# ZynqPS.net
KiCad netlist of a schematic drawn in Altium Designer
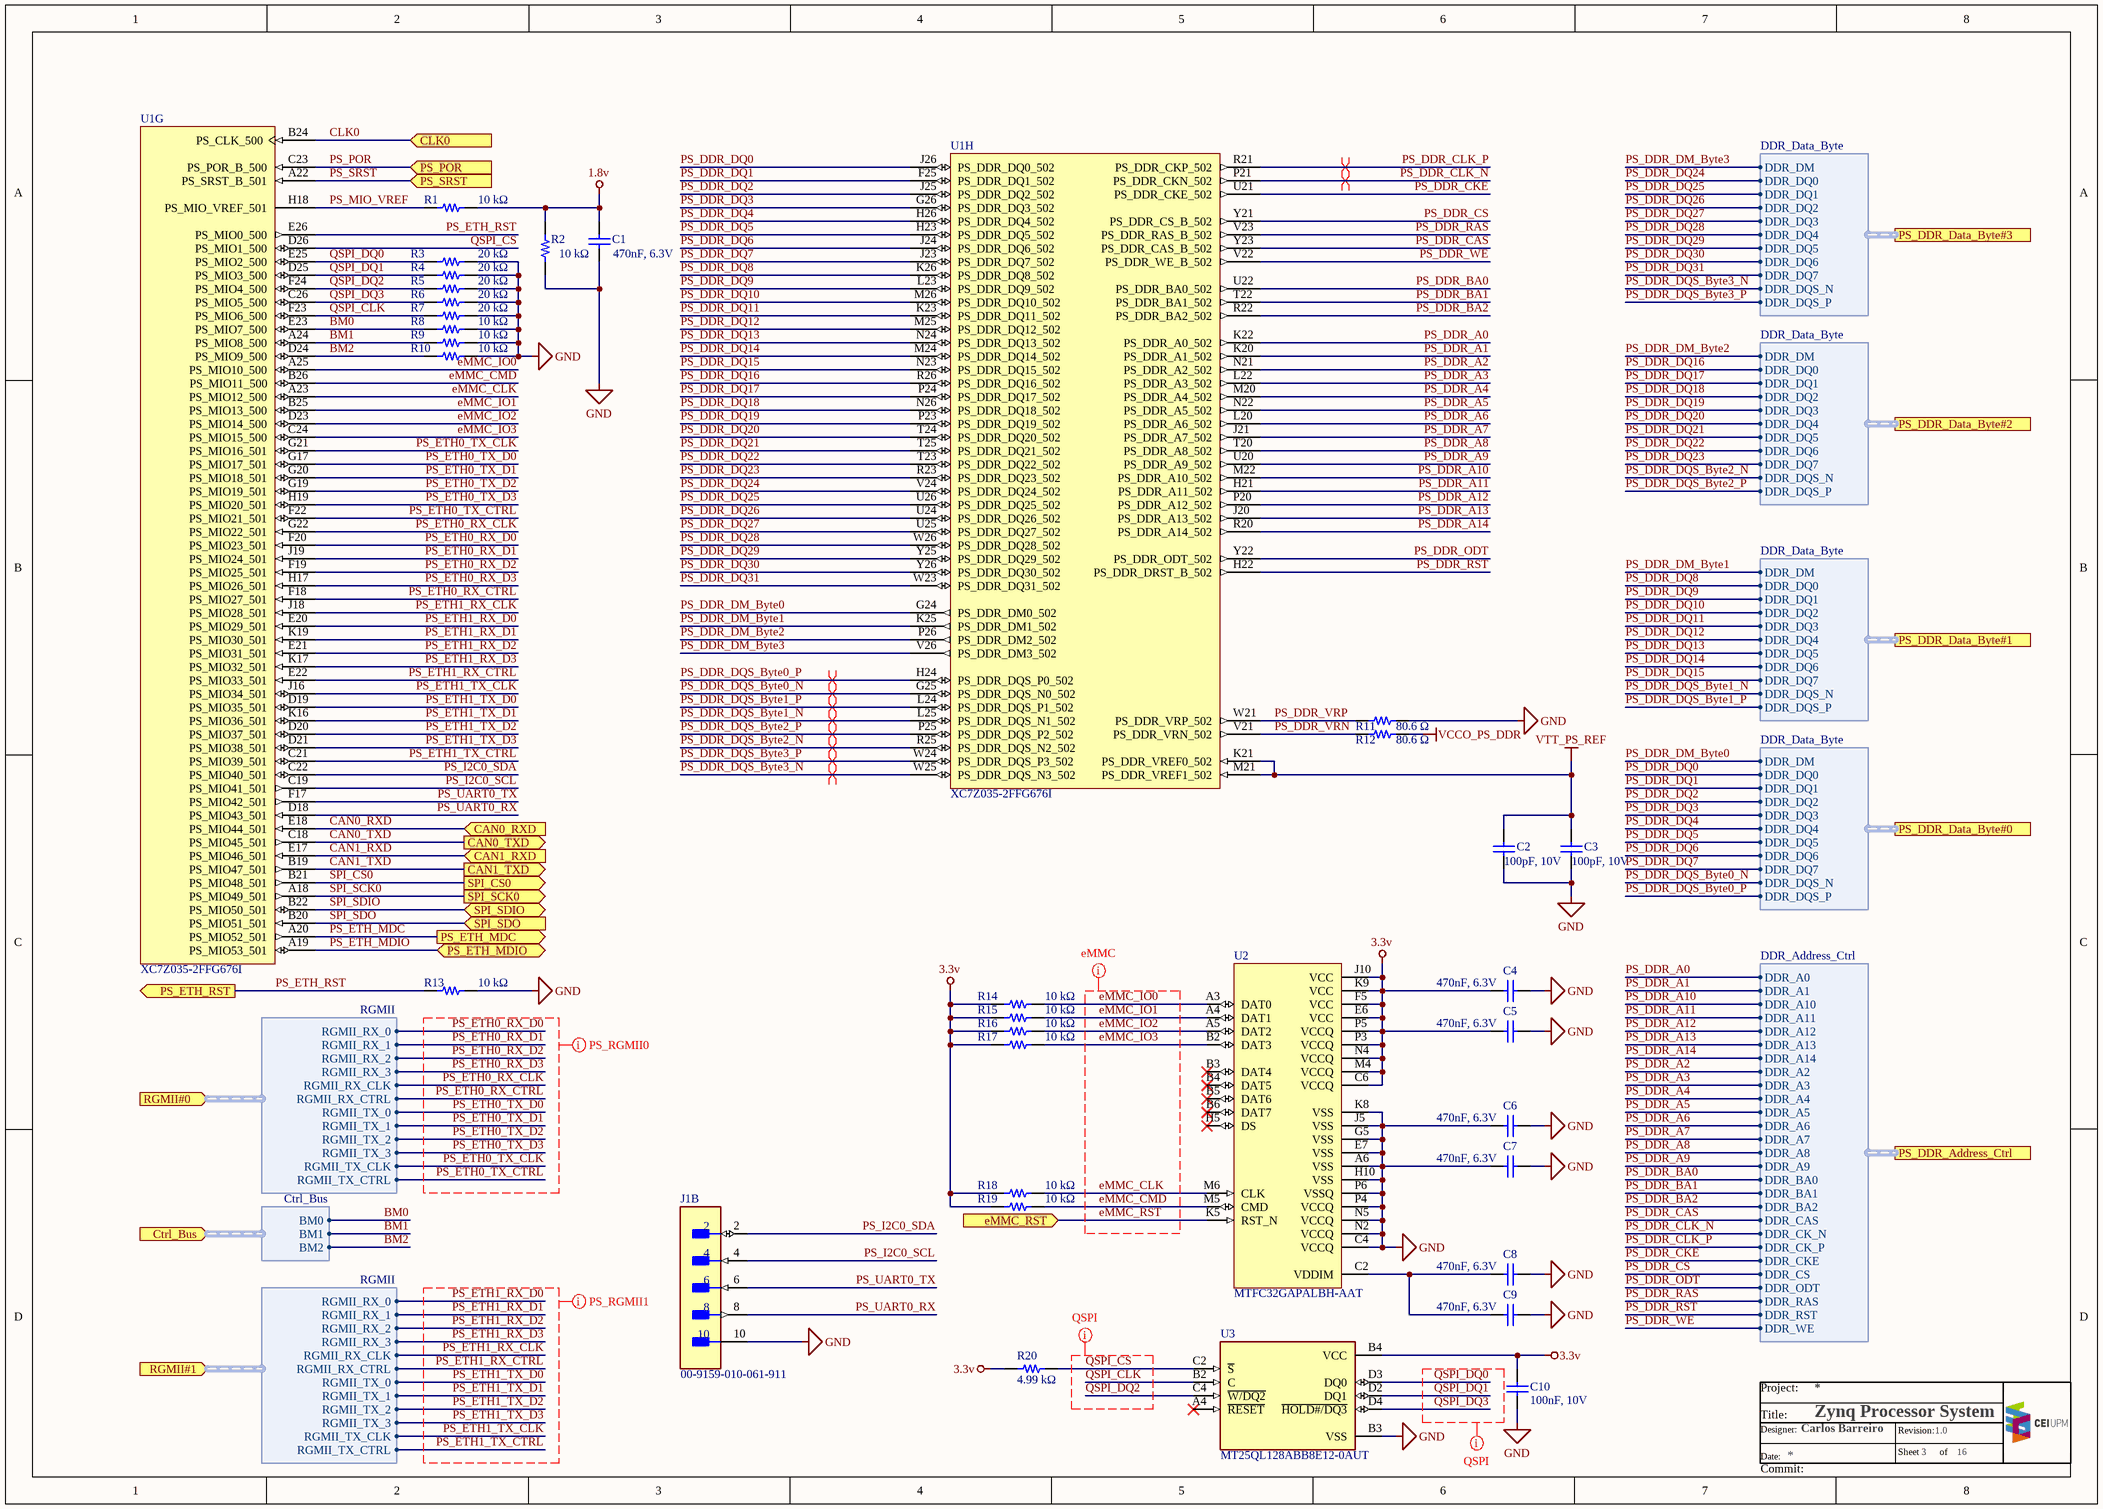
[diagram p0: ZynqPS.SchDoc]

(export (version "E")
  (design (tool "Eeschema 10.0.6"))
  (components
    (comp (ref "C1")
      (value "470nF, 6.3V")
      (footprint "WURTH_WCAP-CSGP_0402")
      (description "WCAP-CSGP Multilayer Ceramic Chip Capacitor, General Purpose, size 0402, X5R, 470nF, 6.3V")
      (fields
        (field (name "MANUFACTURER PART NUMBER") "885012105004")
        (field (name "MANUFACTURER") "Wurth Elektronik")
      )
      (libsource (lib "SpaceVNXBaseBoard") (part "885012105004"))
    )
    (comp (ref "C2")
      (value "100pF, 10V")
      (footprint "WURTH_WCAP-CSGP_0402")
      (description "WCAP-CSGP Multilayer Ceramic Chip Capacitor, General Purpose, size 0402, NP0, 100pF, 10V")
      (fields
        (field (name "MANUFACTURER PART NUMBER") "885012005013")
        (field (name "MANUFACTURER") "Wurth Elektronik")
      )
      (libsource (lib "SpaceVNXBaseBoard") (part "885012005013"))
    )
    (comp (ref "C3")
      (value "100pF, 10V")
      (footprint "WURTH_WCAP-CSGP_0402")
      (description "WCAP-CSGP Multilayer Ceramic Chip Capacitor, General Purpose, size 0402, NP0, 100pF, 10V")
      (fields
        (field (name "MANUFACTURER PART NUMBER") "885012005013")
        (field (name "MANUFACTURER") "Wurth Elektronik")
      )
      (libsource (lib "SpaceVNXBaseBoard") (part "885012005013"))
    )
    (comp (ref "C4")
      (value "470nF, 6.3V")
      (footprint "WURTH_WCAP-CSGP_0402")
      (description "WCAP-CSGP Multilayer Ceramic Chip Capacitor, General Purpose, size 0402, X5R, 470nF, 6.3V")
      (fields
        (field (name "MANUFACTURER PART NUMBER") "885012105004")
        (field (name "MANUFACTURER") "Wurth Elektronik")
      )
      (libsource (lib "SpaceVNXBaseBoard") (part "885012105004"))
    )
    (comp (ref "C5")
      (value "470nF, 6.3V")
      (footprint "WURTH_WCAP-CSGP_0402")
      (description "WCAP-CSGP Multilayer Ceramic Chip Capacitor, General Purpose, size 0402, X5R, 470nF, 6.3V")
      (fields
        (field (name "MANUFACTURER PART NUMBER") "885012105004")
        (field (name "MANUFACTURER") "Wurth Elektronik")
      )
      (libsource (lib "SpaceVNXBaseBoard") (part "885012105004"))
    )
    (comp (ref "C6")
      (value "470nF, 6.3V")
      (footprint "WURTH_WCAP-CSGP_0402")
      (description "WCAP-CSGP Multilayer Ceramic Chip Capacitor, General Purpose, size 0402, X5R, 470nF, 6.3V")
      (fields
        (field (name "MANUFACTURER PART NUMBER") "885012105004")
        (field (name "MANUFACTURER") "Wurth Elektronik")
      )
      (libsource (lib "SpaceVNXBaseBoard") (part "885012105004"))
    )
    (comp (ref "C7")
      (value "470nF, 6.3V")
      (footprint "WURTH_WCAP-CSGP_0402")
      (description "WCAP-CSGP Multilayer Ceramic Chip Capacitor, General Purpose, size 0402, X5R, 470nF, 6.3V")
      (fields
        (field (name "MANUFACTURER PART NUMBER") "885012105004")
        (field (name "MANUFACTURER") "Wurth Elektronik")
      )
      (libsource (lib "SpaceVNXBaseBoard") (part "885012105004"))
    )
    (comp (ref "C8")
      (value "470nF, 6.3V")
      (footprint "WURTH_WCAP-CSGP_0402")
      (description "WCAP-CSGP Multilayer Ceramic Chip Capacitor, General Purpose, size 0402, X5R, 470nF, 6.3V")
      (fields
        (field (name "MANUFACTURER PART NUMBER") "885012105004")
        (field (name "MANUFACTURER") "Wurth Elektronik")
      )
      (libsource (lib "SpaceVNXBaseBoard") (part "885012105004"))
    )
    (comp (ref "C9")
      (value "470nF, 6.3V")
      (footprint "WURTH_WCAP-CSGP_0402")
      (description "WCAP-CSGP Multilayer Ceramic Chip Capacitor, General Purpose, size 0402, X5R, 470nF, 6.3V")
      (fields
        (field (name "MANUFACTURER PART NUMBER") "885012105004")
        (field (name "MANUFACTURER") "Wurth Elektronik")
      )
      (libsource (lib "SpaceVNXBaseBoard") (part "885012105004"))
    )
    (comp (ref "C10")
      (value "100nF, 10V")
      (footprint "WURTH_WCAP-CSGP_0402")
      (description "WCAP-CSGP Multilayer Ceramic Chip Capacitor, General Purpose, size 0402, X7R, 100nF, 10V")
      (fields
        (field (name "MANUFACTURER PART NUMBER") "885012205018")
        (field (name "MANUFACTURER") "Wurth Elektronik")
      )
      (libsource (lib "SpaceVNXBaseBoard") (part "885012205018"))
    )
    (comp (ref "J1")
      (value "00-9159-010-061-911")
      (footprint "KYOCERA_00-9159-010-061-911")
      (description "Coplanar Open Ended Card Edge Connector 10 Pin")
      (libsource (lib "SpaceVNXBaseBoard") (part "00-9159-010-061-911"))
    )
    (comp (ref "R1")
      (value "10 kΩ")
      (footprint "PANASONIC_ERJ2G_0402")
      (description "General Purpose Thick Film Chip Resistors")
      (fields (field (name "MANUFACTURER") "Panasonic"))
      (libsource (lib "SpaceVNXBaseBoard") (part "ERJ2RKF1002X"))
    )
    (comp (ref "R2")
      (value "10 kΩ")
      (footprint "PANASONIC_ERJ2G_0402")
      (description "General Purpose Thick Film Chip Resistors")
      (fields (field (name "MANUFACTURER") "Panasonic"))
      (libsource (lib "SpaceVNXBaseBoard") (part "ERJ2RKF1002X"))
    )
    (comp (ref "R3")
      (value "20 kΩ")
      (footprint "PANASONIC_ERJ2G_0402")
      (description "General Purpose Thick Film Chip Resistors")
      (fields (field (name "MANUFACTURER") "Panasonic"))
      (libsource (lib "SpaceVNXBaseBoard") (part "ERJ2RKF2002X"))
    )
    (comp (ref "R4")
      (value "20 kΩ")
      (footprint "PANASONIC_ERJ2G_0402")
      (description "General Purpose Thick Film Chip Resistors")
      (fields (field (name "MANUFACTURER") "Panasonic"))
      (libsource (lib "SpaceVNXBaseBoard") (part "ERJ2RKF2002X"))
    )
    (comp (ref "R5")
      (value "20 kΩ")
      (footprint "PANASONIC_ERJ2G_0402")
      (description "General Purpose Thick Film Chip Resistors")
      (fields (field (name "MANUFACTURER") "Panasonic"))
      (libsource (lib "SpaceVNXBaseBoard") (part "ERJ2RKF2002X"))
    )
    (comp (ref "R6")
      (value "20 kΩ")
      (footprint "PANASONIC_ERJ2G_0402")
      (description "General Purpose Thick Film Chip Resistors")
      (fields (field (name "MANUFACTURER") "Panasonic"))
      (libsource (lib "SpaceVNXBaseBoard") (part "ERJ2RKF2002X"))
    )
    (comp (ref "R7")
      (value "20 kΩ")
      (footprint "PANASONIC_ERJ2G_0402")
      (description "General Purpose Thick Film Chip Resistors")
      (fields (field (name "MANUFACTURER") "Panasonic"))
      (libsource (lib "SpaceVNXBaseBoard") (part "ERJ2RKF2002X"))
    )
    (comp (ref "R8")
      (value "10 kΩ")
      (footprint "PANASONIC_ERJ2G_0402")
      (description "General Purpose Thick Film Chip Resistors")
      (fields (field (name "MANUFACTURER") "Panasonic"))
      (libsource (lib "SpaceVNXBaseBoard") (part "ERJ2RKF1002X"))
    )
    (comp (ref "R9")
      (value "10 kΩ")
      (footprint "PANASONIC_ERJ2G_0402")
      (description "General Purpose Thick Film Chip Resistors")
      (fields (field (name "MANUFACTURER") "Panasonic"))
      (libsource (lib "SpaceVNXBaseBoard") (part "ERJ2RKF1002X"))
    )
    (comp (ref "R10")
      (value "10 kΩ")
      (footprint "PANASONIC_ERJ2G_0402")
      (description "General Purpose Thick Film Chip Resistors")
      (fields (field (name "MANUFACTURER") "Panasonic"))
      (libsource (lib "SpaceVNXBaseBoard") (part "ERJ2RKF1002X"))
    )
    (comp (ref "R11")
      (value "80.6 Ω")
      (footprint "PANASONIC_ERJ2G_0402")
      (description "General Purpose Thick Film Chip Resistors")
      (fields (field (name "MANUFACTURER") "Panasonic"))
      (libsource (lib "SpaceVNXBaseBoard") (part "ERJ2RKF80R6X"))
    )
    (comp (ref "R12")
      (value "80.6 Ω")
      (footprint "PANASONIC_ERJ2G_0402")
      (description "General Purpose Thick Film Chip Resistors")
      (fields (field (name "MANUFACTURER") "Panasonic"))
      (libsource (lib "SpaceVNXBaseBoard") (part "ERJ2RKF80R6X"))
    )
    (comp (ref "R13")
      (value "10 kΩ")
      (footprint "PANASONIC_ERJ2G_0402")
      (description "General Purpose Thick Film Chip Resistors")
      (fields (field (name "MANUFACTURER") "Panasonic"))
      (libsource (lib "SpaceVNXBaseBoard") (part "ERJ2RKF1002X"))
    )
    (comp (ref "R14")
      (value "10 kΩ")
      (footprint "PANASONIC_ERJ2G_0402")
      (description "General Purpose Thick Film Chip Resistors")
      (fields (field (name "MANUFACTURER") "Panasonic"))
      (libsource (lib "SpaceVNXBaseBoard") (part "ERJ2RKF1002X"))
    )
    (comp (ref "R15")
      (value "10 kΩ")
      (footprint "PANASONIC_ERJ2G_0402")
      (description "General Purpose Thick Film Chip Resistors")
      (fields (field (name "MANUFACTURER") "Panasonic"))
      (libsource (lib "SpaceVNXBaseBoard") (part "ERJ2RKF1002X"))
    )
    (comp (ref "R16")
      (value "10 kΩ")
      (footprint "PANASONIC_ERJ2G_0402")
      (description "General Purpose Thick Film Chip Resistors")
      (fields (field (name "MANUFACTURER") "Panasonic"))
      (libsource (lib "SpaceVNXBaseBoard") (part "ERJ2RKF1002X"))
    )
    (comp (ref "R17")
      (value "10 kΩ")
      (footprint "PANASONIC_ERJ2G_0402")
      (description "General Purpose Thick Film Chip Resistors")
      (fields (field (name "MANUFACTURER") "Panasonic"))
      (libsource (lib "SpaceVNXBaseBoard") (part "ERJ2RKF1002X"))
    )
    (comp (ref "R18")
      (value "10 kΩ")
      (footprint "PANASONIC_ERJ2G_0402")
      (description "General Purpose Thick Film Chip Resistors")
      (fields (field (name "MANUFACTURER") "Panasonic"))
      (libsource (lib "SpaceVNXBaseBoard") (part "ERJ2RKF1002X"))
    )
    (comp (ref "R19")
      (value "10 kΩ")
      (footprint "PANASONIC_ERJ2G_0402")
      (description "General Purpose Thick Film Chip Resistors")
      (fields (field (name "MANUFACTURER") "Panasonic"))
      (libsource (lib "SpaceVNXBaseBoard") (part "ERJ2RKF1002X"))
    )
    (comp (ref "R20")
      (value "4.99 kΩ")
      (footprint "PANASONIC_ERJ2G_0402")
      (description "General Purpose Thick Film Chip Resistors")
      (fields (field (name "MANUFACTURER") "Panasonic"))
      (libsource (lib "SpaceVNXBaseBoard") (part "ERJ2RKF4991X"))
    )
    (comp (ref "U1")
      (value "XC7Z035-2FFG676I")
      (footprint "XILINX_FBG676")
      (fields (field (name "PARTNUMBER") "XC7Z035-2FBG676I") (field (name "GENERIC PART NUMBER") "XC7Z035"))
      (libsource (lib "SpaceVNXBaseBoard") (part "XC7Z035-2FFG676I"))
    )
    (comp (ref "U2")
      (value "MTFC32GAPALBH-AAT")
      (footprint "Micron_BH")
      (description "Flash Memory Managed NAND e.MMC Automotive 32GB")
      (fields (field (name "MF") "Micron Technology"))
      (libsource (lib "SpaceVNXBaseBoard") (part "MTFC32GAPALBH-AAT"))
    )
    (comp (ref "U3")
      (value "MT25QL128ABB8E12-0AUT")
      (footprint "Micron_RW")
      (description "NOR Serial Flash Memory 128Mb 3.3V Multiple I/O Automotive")
      (fields (field (name "MF") "Micron Technology"))
      (libsource (lib "SpaceVNXBaseBoard") (part "MT25QL128ABB8E12-0AUT"))
    )
  )
  (nets
    (net (code "5") (name "/BM0") (class "Default")
      (node (ref "R8") (pin "2") (pinfunction "2_2") (pintype "passive"))
      (node (ref "U1") (pin "E23") (pinfunction "PS_MIO7_500_E23") (pintype "bidirectional"))
    )
    (net (code "6") (name "/BM1") (class "Default")
      (node (ref "R9") (pin "2") (pinfunction "2_2") (pintype "passive"))
      (node (ref "U1") (pin "A24") (pinfunction "PS_MIO8_500_A24") (pintype "bidirectional"))
    )
    (net (code "7") (name "/BM2") (class "Default")
      (node (ref "R10") (pin "2") (pinfunction "2_2") (pintype "passive"))
      (node (ref "U1") (pin "D24") (pinfunction "PS_MIO9_500_D24") (pintype "bidirectional"))
    )
    (net (code "8") (name "/CAN0_RXD") (class "Default")
      (node (ref "U1") (pin "E18") (pinfunction "PS_MIO44_501_E18") (pintype "input"))
    )
    (net (code "9") (name "/CAN0_TXD") (class "Default")
      (node (ref "U1") (pin "C18") (pinfunction "PS_MIO45_501_C18") (pintype "output"))
    )
    (net (code "10") (name "/CAN1_RXD") (class "Default")
      (node (ref "U1") (pin "E17") (pinfunction "PS_MIO46_501_E17") (pintype "input"))
    )
    (net (code "11") (name "/CAN1_TXD") (class "Default")
      (node (ref "U1") (pin "B19") (pinfunction "PS_MIO47_501_B19") (pintype "output"))
    )
    (net (code "12") (name "/CLK0") (class "Default")
      (node (ref "U1") (pin "B24") (pinfunction "PS_CLK_500_B24") (pintype "input"))
    )
    (net (code "13") (name "/PS_DDR_A0") (class "Default")
      (node (ref "U1") (pin "K22") (pinfunction "PS_DDR_A0_502_K22") (pintype "output"))
    )
    (net (code "14") (name "/PS_DDR_A1") (class "Default")
      (node (ref "U1") (pin "K20") (pinfunction "PS_DDR_A1_502_K20") (pintype "output"))
    )
    (net (code "15") (name "/PS_DDR_A2") (class "Default")
      (node (ref "U1") (pin "N21") (pinfunction "PS_DDR_A2_502_N21") (pintype "output"))
    )
    (net (code "16") (name "/PS_DDR_A3") (class "Default")
      (node (ref "U1") (pin "L22") (pinfunction "PS_DDR_A3_502_L22") (pintype "output"))
    )
    (net (code "17") (name "/PS_DDR_A4") (class "Default")
      (node (ref "U1") (pin "M20") (pinfunction "PS_DDR_A4_502_M20") (pintype "output"))
    )
    (net (code "18") (name "/PS_DDR_A5") (class "Default")
      (node (ref "U1") (pin "N22") (pinfunction "PS_DDR_A5_502_N22") (pintype "output"))
    )
    (net (code "19") (name "/PS_DDR_A6") (class "Default")
      (node (ref "U1") (pin "L20") (pinfunction "PS_DDR_A6_502_L20") (pintype "output"))
    )
    (net (code "20") (name "/PS_DDR_A7") (class "Default")
      (node (ref "U1") (pin "J21") (pinfunction "PS_DDR_A7_502_J21") (pintype "output"))
    )
    (net (code "21") (name "/PS_DDR_A8") (class "Default")
      (node (ref "U1") (pin "T20") (pinfunction "PS_DDR_A8_502_T20") (pintype "output"))
    )
    (net (code "22") (name "/PS_DDR_A9") (class "Default")
      (node (ref "U1") (pin "U20") (pinfunction "PS_DDR_A9_502_U20") (pintype "output"))
    )
    (net (code "23") (name "/PS_DDR_A10") (class "Default")
      (node (ref "U1") (pin "M22") (pinfunction "PS_DDR_A10_502_M22") (pintype "output"))
    )
    (net (code "24") (name "/PS_DDR_A11") (class "Default")
      (node (ref "U1") (pin "H21") (pinfunction "PS_DDR_A11_502_H21") (pintype "output"))
    )
    (net (code "25") (name "/PS_DDR_A12") (class "Default")
      (node (ref "U1") (pin "P20") (pinfunction "PS_DDR_A12_502_P20") (pintype "output"))
    )
    (net (code "26") (name "/PS_DDR_A13") (class "Default")
      (node (ref "U1") (pin "J20") (pinfunction "PS_DDR_A13_502_J20") (pintype "output"))
    )
    (net (code "27") (name "/PS_DDR_A14") (class "Default")
      (node (ref "U1") (pin "R20") (pinfunction "PS_DDR_A14_502_R20") (pintype "output"))
    )
    (net (code "28") (name "/PS_DDR_BA0") (class "Default")
      (node (ref "U1") (pin "U22") (pinfunction "PS_DDR_BA0_502_U22") (pintype "output"))
    )
    (net (code "29") (name "/PS_DDR_BA1") (class "Default")
      (node (ref "U1") (pin "T22") (pinfunction "PS_DDR_BA1_502_T22") (pintype "output"))
    )
    (net (code "30") (name "/PS_DDR_BA2") (class "Default")
      (node (ref "U1") (pin "R22") (pinfunction "PS_DDR_BA2_502_R22") (pintype "output"))
    )
    (net (code "31") (name "/PS_DDR_CAS") (class "Default")
      (node (ref "U1") (pin "Y23") (pinfunction "PS_DDR_CAS_B_502_Y23") (pintype "output"))
    )
    (net (code "32") (name "/PS_DDR_CKE") (class "Default")
      (node (ref "U1") (pin "U21") (pinfunction "PS_DDR_CKE_502_U21") (pintype "output"))
    )
    (net (code "33") (name "/PS_DDR_CLK_N") (class "Default")
      (node (ref "U1") (pin "P21") (pinfunction "PS_DDR_CKN_502_P21") (pintype "output"))
    )
    (net (code "34") (name "/PS_DDR_CLK_P") (class "Default")
      (node (ref "U1") (pin "R21") (pinfunction "PS_DDR_CKP_502_R21") (pintype "output"))
    )
    (net (code "35") (name "/PS_DDR_CS") (class "Default")
      (node (ref "U1") (pin "Y21") (pinfunction "PS_DDR_CS_B_502_Y21") (pintype "output"))
    )
    (net (code "36") (name "/PS_DDR_DM_Byte0") (class "Default")
      (node (ref "U1") (pin "G24") (pinfunction "PS_DDR_DM0_502_G24") (pintype "output"))
    )
    (net (code "37") (name "/PS_DDR_DM_Byte1") (class "Default")
      (node (ref "U1") (pin "K25") (pinfunction "PS_DDR_DM1_502_K25") (pintype "output"))
    )
    (net (code "38") (name "/PS_DDR_DM_Byte2") (class "Default")
      (node (ref "U1") (pin "P26") (pinfunction "PS_DDR_DM2_502_P26") (pintype "output"))
    )
    (net (code "39") (name "/PS_DDR_DM_Byte3") (class "Default")
      (node (ref "U1") (pin "V26") (pinfunction "PS_DDR_DM3_502_V26") (pintype "output"))
    )
    (net (code "40") (name "/PS_DDR_DQ0") (class "Default")
      (node (ref "U1") (pin "J26") (pinfunction "PS_DDR_DQ0_502_J26") (pintype "bidirectional"))
    )
    (net (code "41") (name "/PS_DDR_DQ1") (class "Default")
      (node (ref "U1") (pin "F25") (pinfunction "PS_DDR_DQ1_502_F25") (pintype "bidirectional"))
    )
    (net (code "42") (name "/PS_DDR_DQ2") (class "Default")
      (node (ref "U1") (pin "J25") (pinfunction "PS_DDR_DQ2_502_J25") (pintype "bidirectional"))
    )
    (net (code "43") (name "/PS_DDR_DQ3") (class "Default")
      (node (ref "U1") (pin "G26") (pinfunction "PS_DDR_DQ3_502_G26") (pintype "bidirectional"))
    )
    (net (code "44") (name "/PS_DDR_DQ4") (class "Default")
      (node (ref "U1") (pin "H26") (pinfunction "PS_DDR_DQ4_502_H26") (pintype "bidirectional"))
    )
    (net (code "45") (name "/PS_DDR_DQ5") (class "Default")
      (node (ref "U1") (pin "H23") (pinfunction "PS_DDR_DQ5_502_H23") (pintype "bidirectional"))
    )
    (net (code "46") (name "/PS_DDR_DQ6") (class "Default")
      (node (ref "U1") (pin "J24") (pinfunction "PS_DDR_DQ6_502_J24") (pintype "bidirectional"))
    )
    (net (code "47") (name "/PS_DDR_DQ7") (class "Default")
      (node (ref "U1") (pin "J23") (pinfunction "PS_DDR_DQ7_502_J23") (pintype "bidirectional"))
    )
    (net (code "48") (name "/PS_DDR_DQ8") (class "Default")
      (node (ref "U1") (pin "K26") (pinfunction "PS_DDR_DQ8_502_K26") (pintype "bidirectional"))
    )
    (net (code "49") (name "/PS_DDR_DQ9") (class "Default")
      (node (ref "U1") (pin "L23") (pinfunction "PS_DDR_DQ9_502_L23") (pintype "bidirectional"))
    )
    (net (code "50") (name "/PS_DDR_DQ10") (class "Default")
      (node (ref "U1") (pin "M26") (pinfunction "PS_DDR_DQ10_502_M26") (pintype "bidirectional"))
    )
    (net (code "51") (name "/PS_DDR_DQ11") (class "Default")
      (node (ref "U1") (pin "K23") (pinfunction "PS_DDR_DQ11_502_K23") (pintype "bidirectional"))
    )
    (net (code "52") (name "/PS_DDR_DQ12") (class "Default")
      (node (ref "U1") (pin "M25") (pinfunction "PS_DDR_DQ12_502_M25") (pintype "bidirectional"))
    )
    (net (code "53") (name "/PS_DDR_DQ13") (class "Default")
      (node (ref "U1") (pin "N24") (pinfunction "PS_DDR_DQ13_502_N24") (pintype "bidirectional"))
    )
    (net (code "54") (name "/PS_DDR_DQ14") (class "Default")
      (node (ref "U1") (pin "M24") (pinfunction "PS_DDR_DQ14_502_M24") (pintype "bidirectional"))
    )
    (net (code "55") (name "/PS_DDR_DQ15") (class "Default")
      (node (ref "U1") (pin "N23") (pinfunction "PS_DDR_DQ15_502_N23") (pintype "bidirectional"))
    )
    (net (code "56") (name "/PS_DDR_DQ16") (class "Default")
      (node (ref "U1") (pin "R26") (pinfunction "PS_DDR_DQ16_502_R26") (pintype "bidirectional"))
    )
    (net (code "57") (name "/PS_DDR_DQ17") (class "Default")
      (node (ref "U1") (pin "P24") (pinfunction "PS_DDR_DQ17_502_P24") (pintype "bidirectional"))
    )
    (net (code "58") (name "/PS_DDR_DQ18") (class "Default")
      (node (ref "U1") (pin "N26") (pinfunction "PS_DDR_DQ18_502_N26") (pintype "bidirectional"))
    )
    (net (code "59") (name "/PS_DDR_DQ19") (class "Default")
      (node (ref "U1") (pin "P23") (pinfunction "PS_DDR_DQ19_502_P23") (pintype "bidirectional"))
    )
    (net (code "60") (name "/PS_DDR_DQ20") (class "Default")
      (node (ref "U1") (pin "T24") (pinfunction "PS_DDR_DQ20_502_T24") (pintype "bidirectional"))
    )
    (net (code "61") (name "/PS_DDR_DQ21") (class "Default")
      (node (ref "U1") (pin "T25") (pinfunction "PS_DDR_DQ21_502_T25") (pintype "bidirectional"))
    )
    (net (code "62") (name "/PS_DDR_DQ22") (class "Default")
      (node (ref "U1") (pin "T23") (pinfunction "PS_DDR_DQ22_502_T23") (pintype "bidirectional"))
    )
    (net (code "63") (name "/PS_DDR_DQ23") (class "Default")
      (node (ref "U1") (pin "R23") (pinfunction "PS_DDR_DQ23_502_R23") (pintype "bidirectional"))
    )
    (net (code "64") (name "/PS_DDR_DQ24") (class "Default")
      (node (ref "U1") (pin "V24") (pinfunction "PS_DDR_DQ24_502_V24") (pintype "bidirectional"))
    )
    (net (code "65") (name "/PS_DDR_DQ25") (class "Default")
      (node (ref "U1") (pin "U26") (pinfunction "PS_DDR_DQ25_502_U26") (pintype "bidirectional"))
    )
    (net (code "66") (name "/PS_DDR_DQ26") (class "Default")
      (node (ref "U1") (pin "U24") (pinfunction "PS_DDR_DQ26_502_U24") (pintype "bidirectional"))
    )
    (net (code "67") (name "/PS_DDR_DQ27") (class "Default")
      (node (ref "U1") (pin "U25") (pinfunction "PS_DDR_DQ27_502_U25") (pintype "bidirectional"))
    )
    (net (code "68") (name "/PS_DDR_DQ28") (class "Default")
      (node (ref "U1") (pin "W26") (pinfunction "PS_DDR_DQ28_502_W26") (pintype "bidirectional"))
    )
    (net (code "69") (name "/PS_DDR_DQ29") (class "Default")
      (node (ref "U1") (pin "Y25") (pinfunction "PS_DDR_DQ29_502_Y25") (pintype "bidirectional"))
    )
    (net (code "70") (name "/PS_DDR_DQ30") (class "Default")
      (node (ref "U1") (pin "Y26") (pinfunction "PS_DDR_DQ30_502_Y26") (pintype "bidirectional"))
    )
    (net (code "71") (name "/PS_DDR_DQ31") (class "Default")
      (node (ref "U1") (pin "W23") (pinfunction "PS_DDR_DQ31_502_W23") (pintype "bidirectional"))
    )
    (net (code "72") (name "/PS_DDR_DQS_Byte0_N") (class "Default")
      (node (ref "U1") (pin "G25") (pinfunction "PS_DDR_DQS_N0_502_G25") (pintype "bidirectional"))
    )
    (net (code "73") (name "/PS_DDR_DQS_Byte0_P") (class "Default")
      (node (ref "U1") (pin "H24") (pinfunction "PS_DDR_DQS_P0_502_H24") (pintype "bidirectional"))
    )
    (net (code "74") (name "/PS_DDR_DQS_Byte1_N") (class "Default")
      (node (ref "U1") (pin "L25") (pinfunction "PS_DDR_DQS_N1_502_L25") (pintype "bidirectional"))
    )
    (net (code "75") (name "/PS_DDR_DQS_Byte1_P") (class "Default")
      (node (ref "U1") (pin "L24") (pinfunction "PS_DDR_DQS_P1_502_L24") (pintype "bidirectional"))
    )
    (net (code "76") (name "/PS_DDR_DQS_Byte2_N") (class "Default")
      (node (ref "U1") (pin "R25") (pinfunction "PS_DDR_DQS_N2_502_R25") (pintype "bidirectional"))
    )
    (net (code "77") (name "/PS_DDR_DQS_Byte2_P") (class "Default")
      (node (ref "U1") (pin "P25") (pinfunction "PS_DDR_DQS_P2_502_P25") (pintype "bidirectional"))
    )
    (net (code "78") (name "/PS_DDR_DQS_Byte3_N") (class "Default")
      (node (ref "U1") (pin "W25") (pinfunction "PS_DDR_DQS_N3_502_W25") (pintype "bidirectional"))
    )
    (net (code "79") (name "/PS_DDR_DQS_Byte3_P") (class "Default")
      (node (ref "U1") (pin "W24") (pinfunction "PS_DDR_DQS_P3_502_W24") (pintype "bidirectional"))
    )
    (net (code "80") (name "/PS_DDR_ODT") (class "Default")
      (node (ref "U1") (pin "Y22") (pinfunction "PS_DDR_ODT_502_Y22") (pintype "output"))
    )
    (net (code "81") (name "/PS_DDR_RAS") (class "Default")
      (node (ref "U1") (pin "V23") (pinfunction "PS_DDR_RAS_B_502_V23") (pintype "output"))
    )
    (net (code "82") (name "/PS_DDR_RST") (class "Default")
      (node (ref "U1") (pin "H22") (pinfunction "PS_DDR_DRST_B_502_H22") (pintype "output"))
    )
    (net (code "83") (name "/PS_DDR_VRN") (class "Default")
      (node (ref "R12") (pin "1") (pinfunction "1_1") (pintype "passive"))
      (node (ref "U1") (pin "V21") (pinfunction "PS_DDR_VRN_502_V21") (pintype "output"))
    )
    (net (code "84") (name "/PS_DDR_VRP") (class "Default")
      (node (ref "R11") (pin "1") (pinfunction "1_1") (pintype "passive"))
      (node (ref "U1") (pin "W21") (pinfunction "PS_DDR_VRP_502_W21") (pintype "output"))
    )
    (net (code "85") (name "/PS_DDR_WE") (class "Default")
      (node (ref "U1") (pin "V22") (pinfunction "PS_DDR_WE_B_502_V22") (pintype "output"))
    )
    (net (code "86") (name "/PS_ETH0_RX_CLK") (class "Default")
      (node (ref "U1") (pin "G22") (pinfunction "PS_MIO22_501_G22") (pintype "input"))
    )
    (net (code "87") (name "/PS_ETH0_RX_CTRL") (class "Default")
      (node (ref "U1") (pin "F18") (pinfunction "PS_MIO27_501_F18") (pintype "input"))
    )
    (net (code "88") (name "/PS_ETH0_RX_D0") (class "Default")
      (node (ref "U1") (pin "F20") (pinfunction "PS_MIO23_501_F20") (pintype "input"))
    )
    (net (code "89") (name "/PS_ETH0_RX_D1") (class "Default")
      (node (ref "U1") (pin "J19") (pinfunction "PS_MIO24_501_J19") (pintype "input"))
    )
    (net (code "90") (name "/PS_ETH0_RX_D2") (class "Default")
      (node (ref "U1") (pin "F19") (pinfunction "PS_MIO25_501_F19") (pintype "input"))
    )
    (net (code "91") (name "/PS_ETH0_RX_D3") (class "Default")
      (node (ref "U1") (pin "H17") (pinfunction "PS_MIO26_501_H17") (pintype "input"))
    )
    (net (code "92") (name "/PS_ETH0_TX_CLK") (class "Default")
      (node (ref "U1") (pin "G21") (pinfunction "PS_MIO16_501_G21") (pintype "bidirectional"))
    )
    (net (code "93") (name "/PS_ETH0_TX_CTRL") (class "Default")
      (node (ref "U1") (pin "F22") (pinfunction "PS_MIO21_501_F22") (pintype "bidirectional"))
    )
    (net (code "94") (name "/PS_ETH0_TX_D0") (class "Default")
      (node (ref "U1") (pin "G17") (pinfunction "PS_MIO17_501_G17") (pintype "bidirectional"))
    )
    (net (code "95") (name "/PS_ETH0_TX_D1") (class "Default")
      (node (ref "U1") (pin "G20") (pinfunction "PS_MIO18_501_G20") (pintype "bidirectional"))
    )
    (net (code "96") (name "/PS_ETH0_TX_D2") (class "Default")
      (node (ref "U1") (pin "G19") (pinfunction "PS_MIO19_501_G19") (pintype "bidirectional"))
    )
    (net (code "97") (name "/PS_ETH0_TX_D3") (class "Default")
      (node (ref "U1") (pin "H19") (pinfunction "PS_MIO20_501_H19") (pintype "bidirectional"))
    )
    (net (code "98") (name "/PS_ETH1_RX_CLK") (class "Default")
      (node (ref "U1") (pin "J18") (pinfunction "PS_MIO28_501_J18") (pintype "input"))
    )
    (net (code "99") (name "/PS_ETH1_RX_CTRL") (class "Default")
      (node (ref "U1") (pin "E22") (pinfunction "PS_MIO33_501_E22") (pintype "input"))
    )
    (net (code "100") (name "/PS_ETH1_RX_D0") (class "Default")
      (node (ref "U1") (pin "E20") (pinfunction "PS_MIO29_501_E20") (pintype "input"))
    )
    (net (code "101") (name "/PS_ETH1_RX_D1") (class "Default")
      (node (ref "U1") (pin "K19") (pinfunction "PS_MIO30_501_K19") (pintype "input"))
    )
    (net (code "102") (name "/PS_ETH1_RX_D2") (class "Default")
      (node (ref "U1") (pin "E21") (pinfunction "PS_MIO31_501_E21") (pintype "input"))
    )
    (net (code "103") (name "/PS_ETH1_RX_D3") (class "Default")
      (node (ref "U1") (pin "K17") (pinfunction "PS_MIO32_501_K17") (pintype "input"))
    )
    (net (code "104") (name "/PS_ETH1_TX_CLK") (class "Default")
      (node (ref "U1") (pin "J16") (pinfunction "PS_MIO34_501_J16") (pintype "bidirectional"))
    )
    (net (code "105") (name "/PS_ETH1_TX_CTRL") (class "Default")
      (node (ref "U1") (pin "C21") (pinfunction "PS_MIO39_501_C21") (pintype "bidirectional"))
    )
    (net (code "106") (name "/PS_ETH1_TX_D0") (class "Default")
      (node (ref "U1") (pin "D19") (pinfunction "PS_MIO35_501_D19") (pintype "bidirectional"))
    )
    (net (code "107") (name "/PS_ETH1_TX_D1") (class "Default")
      (node (ref "U1") (pin "K16") (pinfunction "PS_MIO36_501_K16") (pintype "bidirectional"))
    )
    (net (code "108") (name "/PS_ETH1_TX_D2") (class "Default")
      (node (ref "U1") (pin "D20") (pinfunction "PS_MIO37_501_D20") (pintype "bidirectional"))
    )
    (net (code "109") (name "/PS_ETH1_TX_D3") (class "Default")
      (node (ref "U1") (pin "D21") (pinfunction "PS_MIO38_501_D21") (pintype "bidirectional"))
    )
    (net (code "110") (name "/PS_ETH_MDC") (class "Default")
      (node (ref "U1") (pin "A20") (pinfunction "PS_MIO52_501_A20") (pintype "output"))
    )
    (net (code "111") (name "/PS_ETH_MDIO") (class "Default")
      (node (ref "U1") (pin "A19") (pinfunction "PS_MIO53_501_A19") (pintype "bidirectional"))
    )
    (net (code "112") (name "/PS_ETH_RST") (class "Default")
      (node (ref "R13") (pin "2") (pinfunction "2_2") (pintype "passive"))
      (node (ref "U1") (pin "E26") (pinfunction "PS_MIO0_500_E26") (pintype "output"))
    )
    (net (code "113") (name "/PS_I2C0_SCL") (class "Default")
      (node (ref "J1") (pin "4") (pinfunction "4_4") (pintype "input"))
      (node (ref "U1") (pin "C19") (pinfunction "PS_MIO41_501_C19") (pintype "output"))
    )
    (net (code "114") (name "/PS_I2C0_SDA") (class "Default")
      (node (ref "J1") (pin "2") (pinfunction "2_2") (pintype "bidirectional"))
      (node (ref "U1") (pin "C22") (pinfunction "PS_MIO40_501_C22") (pintype "bidirectional"))
    )
    (net (code "115") (name "/PS_MIO_VREF") (class "Default")
      (node (ref "R1") (pin "2") (pinfunction "2_2") (pintype "passive"))
      (node (ref "U1") (pin "H18") (pinfunction "PS_MIO_VREF_501_H18") (pintype "passive"))
    )
    (net (code "116") (name "/PS_POR") (class "Default")
      (node (ref "U1") (pin "C23") (pinfunction "PS_POR_B_500_C23") (pintype "input"))
    )
    (net (code "117") (name "/PS_SRST") (class "Default")
      (node (ref "U1") (pin "A22") (pinfunction "PS_SRST_B_501_A22") (pintype "input"))
    )
    (net (code "118") (name "/PS_UART0_RX") (class "Default")
      (node (ref "J1") (pin "8") (pinfunction "8_8") (pintype "output"))
      (node (ref "U1") (pin "D18") (pinfunction "PS_MIO43_501_D18") (pintype "input"))
    )
    (net (code "119") (name "/PS_UART0_TX") (class "Default")
      (node (ref "J1") (pin "6") (pinfunction "6_6") (pintype "input"))
      (node (ref "U1") (pin "F17") (pinfunction "PS_MIO42_501_F17") (pintype "output"))
    )
    (net (code "120") (name "/QSPI_CLK") (class "Default")
      (node (ref "R7") (pin "1") (pinfunction "1_1") (pintype "passive"))
      (node (ref "U1") (pin "F23") (pinfunction "PS_MIO6_500_F23") (pintype "bidirectional"))
      (node (ref "U3") (pin "B2") (pinfunction "C_B2") (pintype "input"))
    )
    (net (code "121") (name "/QSPI_CS") (class "Default")
      (node (ref "R20") (pin "2") (pinfunction "2_2") (pintype "passive"))
      (node (ref "U1") (pin "D26") (pinfunction "PS_MIO1_500_D26") (pintype "bidirectional"))
      (node (ref "U3") (pin "C2") (pinfunction "~{S}_C2") (pintype "input"))
    )
    (net (code "122") (name "/QSPI_DQ0") (class "Default")
      (node (ref "R3") (pin "1") (pinfunction "1_1") (pintype "passive"))
      (node (ref "U1") (pin "E25") (pinfunction "PS_MIO2_500_E25") (pintype "bidirectional"))
      (node (ref "U3") (pin "D3") (pinfunction "DQ0_D3") (pintype "bidirectional"))
    )
    (net (code "123") (name "/QSPI_DQ1") (class "Default")
      (node (ref "R4") (pin "1") (pinfunction "1_1") (pintype "passive"))
      (node (ref "U1") (pin "D25") (pinfunction "PS_MIO3_500_D25") (pintype "bidirectional"))
      (node (ref "U3") (pin "D2") (pinfunction "DQ1_D2") (pintype "bidirectional"))
    )
    (net (code "124") (name "/QSPI_DQ2") (class "Default")
      (node (ref "R5") (pin "1") (pinfunction "1_1") (pintype "passive"))
      (node (ref "U1") (pin "F24") (pinfunction "PS_MIO4_500_F24") (pintype "bidirectional"))
      (node (ref "U3") (pin "C4") (pinfunction "~{W/DQ2}_C4") (pintype "input"))
    )
    (net (code "125") (name "/QSPI_DQ3") (class "Default")
      (node (ref "R6") (pin "1") (pinfunction "1_1") (pintype "passive"))
      (node (ref "U1") (pin "C26") (pinfunction "PS_MIO5_500_C26") (pintype "bidirectional"))
      (node (ref "U3") (pin "D4") (pinfunction "~{HOLD#/DQ3}_D4") (pintype "bidirectional"))
    )
    (net (code "126") (name "/SPI_CS0") (class "Default")
      (node (ref "U1") (pin "B21") (pinfunction "PS_MIO48_501_B21") (pintype "output"))
    )
    (net (code "127") (name "/SPI_SCK0") (class "Default")
      (node (ref "U1") (pin "A18") (pinfunction "PS_MIO49_501_A18") (pintype "output"))
    )
    (net (code "128") (name "/SPI_SDIO") (class "Default")
      (node (ref "U1") (pin "B22") (pinfunction "PS_MIO50_501_B22") (pintype "bidirectional"))
    )
    (net (code "129") (name "/SPI_SDO") (class "Default")
      (node (ref "U1") (pin "B20") (pinfunction "PS_MIO51_501_B20") (pintype "input"))
    )
    (net (code "130") (name "/eMMC_CLK") (class "Default")
      (node (ref "R18") (pin "1") (pinfunction "1_1") (pintype "passive"))
      (node (ref "U1") (pin "A23") (pinfunction "PS_MIO12_500_A23") (pintype "bidirectional"))
      (node (ref "U2") (pin "M6") (pinfunction "CLK_M6") (pintype "input"))
    )
    (net (code "131") (name "/eMMC_CMD") (class "Default")
      (node (ref "R19") (pin "1") (pinfunction "1_1") (pintype "passive"))
      (node (ref "U1") (pin "B26") (pinfunction "PS_MIO11_500_B26") (pintype "bidirectional"))
      (node (ref "U2") (pin "M5") (pinfunction "CMD_M5") (pintype "bidirectional"))
    )
    (net (code "132") (name "/eMMC_IO0") (class "Default")
      (node (ref "R14") (pin "1") (pinfunction "1_1") (pintype "passive"))
      (node (ref "U1") (pin "A25") (pinfunction "PS_MIO10_500_A25") (pintype "bidirectional"))
      (node (ref "U2") (pin "A3") (pinfunction "DAT0_A3") (pintype "bidirectional"))
    )
    (net (code "133") (name "/eMMC_IO1") (class "Default")
      (node (ref "R15") (pin "1") (pinfunction "1_1") (pintype "passive"))
      (node (ref "U1") (pin "B25") (pinfunction "PS_MIO13_500_B25") (pintype "bidirectional"))
      (node (ref "U2") (pin "A4") (pinfunction "DAT1_A4") (pintype "bidirectional"))
    )
    (net (code "134") (name "/eMMC_IO2") (class "Default")
      (node (ref "R16") (pin "1") (pinfunction "1_1") (pintype "passive"))
      (node (ref "U1") (pin "D23") (pinfunction "PS_MIO14_500_D23") (pintype "bidirectional"))
      (node (ref "U2") (pin "A5") (pinfunction "DAT2_A5") (pintype "bidirectional"))
    )
    (net (code "135") (name "/eMMC_IO3") (class "Default")
      (node (ref "R17") (pin "1") (pinfunction "1_1") (pintype "passive"))
      (node (ref "U1") (pin "C24") (pinfunction "PS_MIO15_500_C24") (pintype "bidirectional"))
      (node (ref "U2") (pin "B2") (pinfunction "DAT3_B2") (pintype "bidirectional"))
    )
    (net (code "136") (name "/eMMC_RST") (class "Default")
      (node (ref "U2") (pin "K5") (pinfunction "RST_N_K5") (pintype "input"))
    )
    (net (code "141") (name "1.8v") (class "Default")
      (node (ref "C1") (pin "1") (pinfunction "1_1") (pintype "passive"))
      (node (ref "R1") (pin "1") (pinfunction "1_1") (pintype "passive"))
      (node (ref "R2") (pin "2") (pinfunction "2_2") (pintype "passive"))
    )
    (net (code "142") (name "3.3v") (class "Default")
      (node (ref "C10") (pin "2") (pinfunction "2_2") (pintype "passive"))
      (node (ref "C4") (pin "1") (pinfunction "1_1") (pintype "passive"))
      (node (ref "C5") (pin "1") (pinfunction "1_1") (pintype "passive"))
      (node (ref "R14") (pin "2") (pinfunction "2_2") (pintype "passive"))
      (node (ref "R15") (pin "2") (pinfunction "2_2") (pintype "passive"))
      (node (ref "R16") (pin "2") (pinfunction "2_2") (pintype "passive"))
      (node (ref "R17") (pin "2") (pinfunction "2_2") (pintype "passive"))
      (node (ref "R18") (pin "2") (pinfunction "2_2") (pintype "passive"))
      (node (ref "R19") (pin "2") (pinfunction "2_2") (pintype "passive"))
      (node (ref "R20") (pin "1") (pinfunction "1_1") (pintype "passive"))
      (node (ref "U2") (pin "C6") (pinfunction "VCCQ_C6") (pintype "power_in"))
      (node (ref "U2") (pin "E6") (pinfunction "VCC_E6") (pintype "power_in"))
      (node (ref "U2") (pin "F5") (pinfunction "VCC_F5") (pintype "power_in"))
      (node (ref "U2") (pin "J10") (pinfunction "VCC_J10") (pintype "power_in"))
      (node (ref "U2") (pin "K9") (pinfunction "VCC_K9") (pintype "power_in"))
      (node (ref "U2") (pin "M4") (pinfunction "VCCQ_M4") (pintype "power_in"))
      (node (ref "U2") (pin "N4") (pinfunction "VCCQ_N4") (pintype "power_in"))
      (node (ref "U2") (pin "P3") (pinfunction "VCCQ_P3") (pintype "power_in"))
      (node (ref "U2") (pin "P5") (pinfunction "VCCQ_P5") (pintype "power_in"))
      (node (ref "U3") (pin "B4") (pinfunction "VCC_B4") (pintype "power_in"))
    )
    (net (code "143") (name "GND") (class "Default")
      (node (ref "C1") (pin "2") (pinfunction "2_2") (pintype "passive"))
      (node (ref "C10") (pin "1") (pinfunction "1_1") (pintype "passive"))
      (node (ref "C2") (pin "1") (pinfunction "1_1") (pintype "passive"))
      (node (ref "C3") (pin "1") (pinfunction "1_1") (pintype "passive"))
      (node (ref "C4") (pin "2") (pinfunction "2_2") (pintype "passive"))
      (node (ref "C5") (pin "2") (pinfunction "2_2") (pintype "passive"))
      (node (ref "C6") (pin "1") (pinfunction "1_1") (pintype "passive"))
      (node (ref "C6") (pin "2") (pinfunction "2_2") (pintype "passive"))
      (node (ref "C7") (pin "1") (pinfunction "1_1") (pintype "passive"))
      (node (ref "C7") (pin "2") (pinfunction "2_2") (pintype "passive"))
      (node (ref "C8") (pin "2") (pinfunction "2_2") (pintype "passive"))
      (node (ref "C9") (pin "2") (pinfunction "2_2") (pintype "passive"))
      (node (ref "J1") (pin "10") (pinfunction "10_10") (pintype "passive"))
      (node (ref "R10") (pin "1") (pinfunction "1_1") (pintype "passive"))
      (node (ref "R11") (pin "2") (pinfunction "2_2") (pintype "passive"))
      (node (ref "R13") (pin "1") (pinfunction "1_1") (pintype "passive"))
      (node (ref "R2") (pin "1") (pinfunction "1_1") (pintype "passive"))
      (node (ref "R3") (pin "2") (pinfunction "2_2") (pintype "passive"))
      (node (ref "R4") (pin "2") (pinfunction "2_2") (pintype "passive"))
      (node (ref "R5") (pin "2") (pinfunction "2_2") (pintype "passive"))
      (node (ref "R6") (pin "2") (pinfunction "2_2") (pintype "passive"))
      (node (ref "R7") (pin "2") (pinfunction "2_2") (pintype "passive"))
      (node (ref "R8") (pin "1") (pinfunction "1_1") (pintype "passive"))
      (node (ref "R9") (pin "1") (pinfunction "1_1") (pintype "passive"))
      (node (ref "U2") (pin "A6") (pinfunction "VSS_A6") (pintype "power_in"))
      (node (ref "U2") (pin "C4") (pinfunction "VCCQ_C4") (pintype "power_in"))
      (node (ref "U2") (pin "E7") (pinfunction "VSS_E7") (pintype "power_in"))
      (node (ref "U2") (pin "G5") (pinfunction "VSS_G5") (pintype "power_in"))
      (node (ref "U2") (pin "H10") (pinfunction "VSS_H10") (pintype "power_in"))
      (node (ref "U2") (pin "J5") (pinfunction "VSS_J5") (pintype "power_in"))
      (node (ref "U2") (pin "K8") (pinfunction "VSS_K8") (pintype "power_in"))
      (node (ref "U2") (pin "N2") (pinfunction "VCCQ_N2") (pintype "power_in"))
      (node (ref "U2") (pin "N5") (pinfunction "VCCQ_N5") (pintype "power_in"))
      (node (ref "U2") (pin "P4") (pinfunction "VCCQ_P4") (pintype "power_in"))
      (node (ref "U2") (pin "P6") (pinfunction "VSSQ_P6") (pintype "power_in"))
      (node (ref "U3") (pin "B3") (pinfunction "VSS_B3") (pintype "power_in"))
    )
    (net (code "144") (name "Net-(U2-VDDIM)") (class "Default")
      (node (ref "C8") (pin "1") (pinfunction "1_1") (pintype "passive"))
      (node (ref "C9") (pin "1") (pinfunction "1_1") (pintype "passive"))
      (node (ref "U2") (pin "C2") (pinfunction "VDDIM_C2") (pintype "power_in"))
    )
    (net (code "145") (name "VCCO_PS_DDR") (class "Default")
      (node (ref "R12") (pin "2") (pinfunction "2_2") (pintype "passive"))
    )
    (net (code "146") (name "VTT_PS_REF") (class "Default")
      (node (ref "C2") (pin "2") (pinfunction "2_2") (pintype "passive"))
      (node (ref "C3") (pin "2") (pinfunction "2_2") (pintype "passive"))
      (node (ref "U1") (pin "K21") (pinfunction "PS_DDR_VREF0_502_K21") (pintype "input"))
      (node (ref "U1") (pin "M21") (pinfunction "PS_DDR_VREF1_502_M21") (pintype "input"))
    )
    (net (code "147") (name "unconnected-(U2-DAT4-PadB3)") (class "Default")
      (node (ref "U2") (pin "B3") (pinfunction "DAT4_B3") (pintype "bidirectional+no_connect"))
    )
    (net (code "148") (name "unconnected-(U2-DAT5-PadB4)") (class "Default")
      (node (ref "U2") (pin "B4") (pinfunction "DAT5_B4") (pintype "bidirectional+no_connect"))
    )
    (net (code "149") (name "unconnected-(U2-DAT6-PadB5)") (class "Default")
      (node (ref "U2") (pin "B5") (pinfunction "DAT6_B5") (pintype "bidirectional+no_connect"))
    )
    (net (code "150") (name "unconnected-(U2-DAT7-PadB6)") (class "Default")
      (node (ref "U2") (pin "B6") (pinfunction "DAT7_B6") (pintype "bidirectional+no_connect"))
    )
    (net (code "151") (name "unconnected-(U2-DS-PadH5)") (class "Default")
      (node (ref "U2") (pin "H5") (pinfunction "DS_H5") (pintype "bidirectional+no_connect"))
    )
    (net (code "152") (name "unconnected-(U3-~{RESET}-PadA4)") (class "Default")
      (node (ref "U3") (pin "A4") (pinfunction "~{RESET}_A4") (pintype "input+no_connect"))
    )
  )
)
